# Power_Regulator.net
KiCad netlist of a schematic drawn in Altium Designer
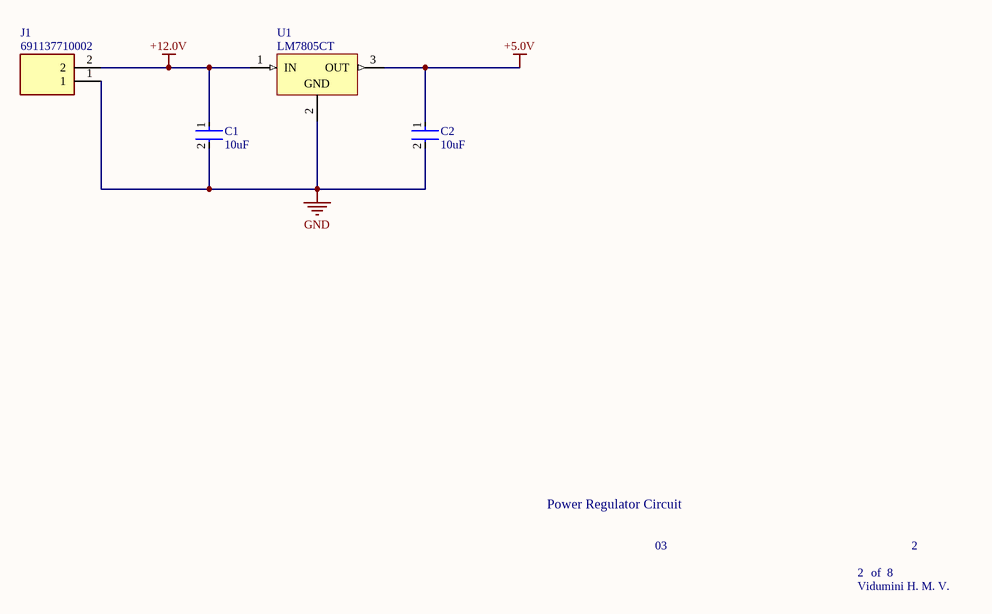
[diagram p0: Power Regulator.SchDoc]

(export (version "E")
  (design (tool "Eeschema 10.0.6"))
  (components
    (comp (ref "C1")
      (value "10uF")
      (footprint "FP-1206-L_3_2_0_2-W_1_6_0-IPC_B")
      (description "General Purpose Ceramic Capacitor, 1206, 10uF, 10%, X5R, 15%, 25V")
      (fields (field (name "TOLERANCE") "10%") (field (name "VOLTAGE") "25V"))
      (libsource (lib "Altium Content Vault") (part "02cd4be3c70576c341d710602a673aa"))
    )
    (comp (ref "C2")
      (value "10uF")
      (footprint "FP-1206-L_3_2_0_2-W_1_6_0-IPC_B")
      (description "General Purpose Ceramic Capacitor, 1206, 10uF, 10%, X5R, 15%, 25V")
      (fields (field (name "TOLERANCE") "10%") (field (name "VOLTAGE") "25V"))
      (libsource (lib "Altium Content Vault") (part "02cd4be3c70576c341d710602a673aa"))
    )
    (comp (ref "J1")
      (value "691137710002")
      (footprint "SamacSys:SHDR2W70P0X500_1X2_1000X750X1160P")
      (description "Connector")
      (fields (field (name "MOUSER PART NUMBER") "710-691137710002"))
      (libsource (lib "*") (part "691137710002"))
    )
    (comp (ref "U1")
      (value "LM7805CT")
      (footprint "FAIR-TO-220-3")
      (description "Positive Voltage Regulator, 5 V, 1 A, -40 to 125 degC, 3-Pin TO-220, RoHS, Tube")
      (fields (field (name "MANUFACTURER") "FairchildSemiconductor"))
      (libsource (lib "Altium Content Vault") (part "FAIR-LM7805CT-TO220-3"))
    )
  )
  (nets
    (net (code "1") (name "+5.0V") (class "Default")
      (node (ref "C2") (pin "1") (pinfunction "1_1") (pintype "passive"))
      (node (ref "U1") (pin "3") (pinfunction "OUT_3") (pintype "output"))
    )
    (net (code "2") (name "+12.0V") (class "Default")
      (node (ref "C1") (pin "1") (pinfunction "1_1") (pintype "passive"))
      (node (ref "J1") (pin "2") (pinfunction "2_2") (pintype "passive"))
      (node (ref "U1") (pin "1") (pinfunction "IN_1") (pintype "input"))
    )
    (net (code "3") (name "GND") (class "Default")
      (node (ref "C1") (pin "2") (pinfunction "2_2") (pintype "passive"))
      (node (ref "C2") (pin "2") (pinfunction "2_2") (pintype "passive"))
      (node (ref "J1") (pin "1") (pinfunction "1_1") (pintype "passive"))
      (node (ref "U1") (pin "2") (pinfunction "GND_2") (pintype "power_in"))
    )
  )
)
